# power.net
KiCad netlist of a schematic drawn in Altium Designer
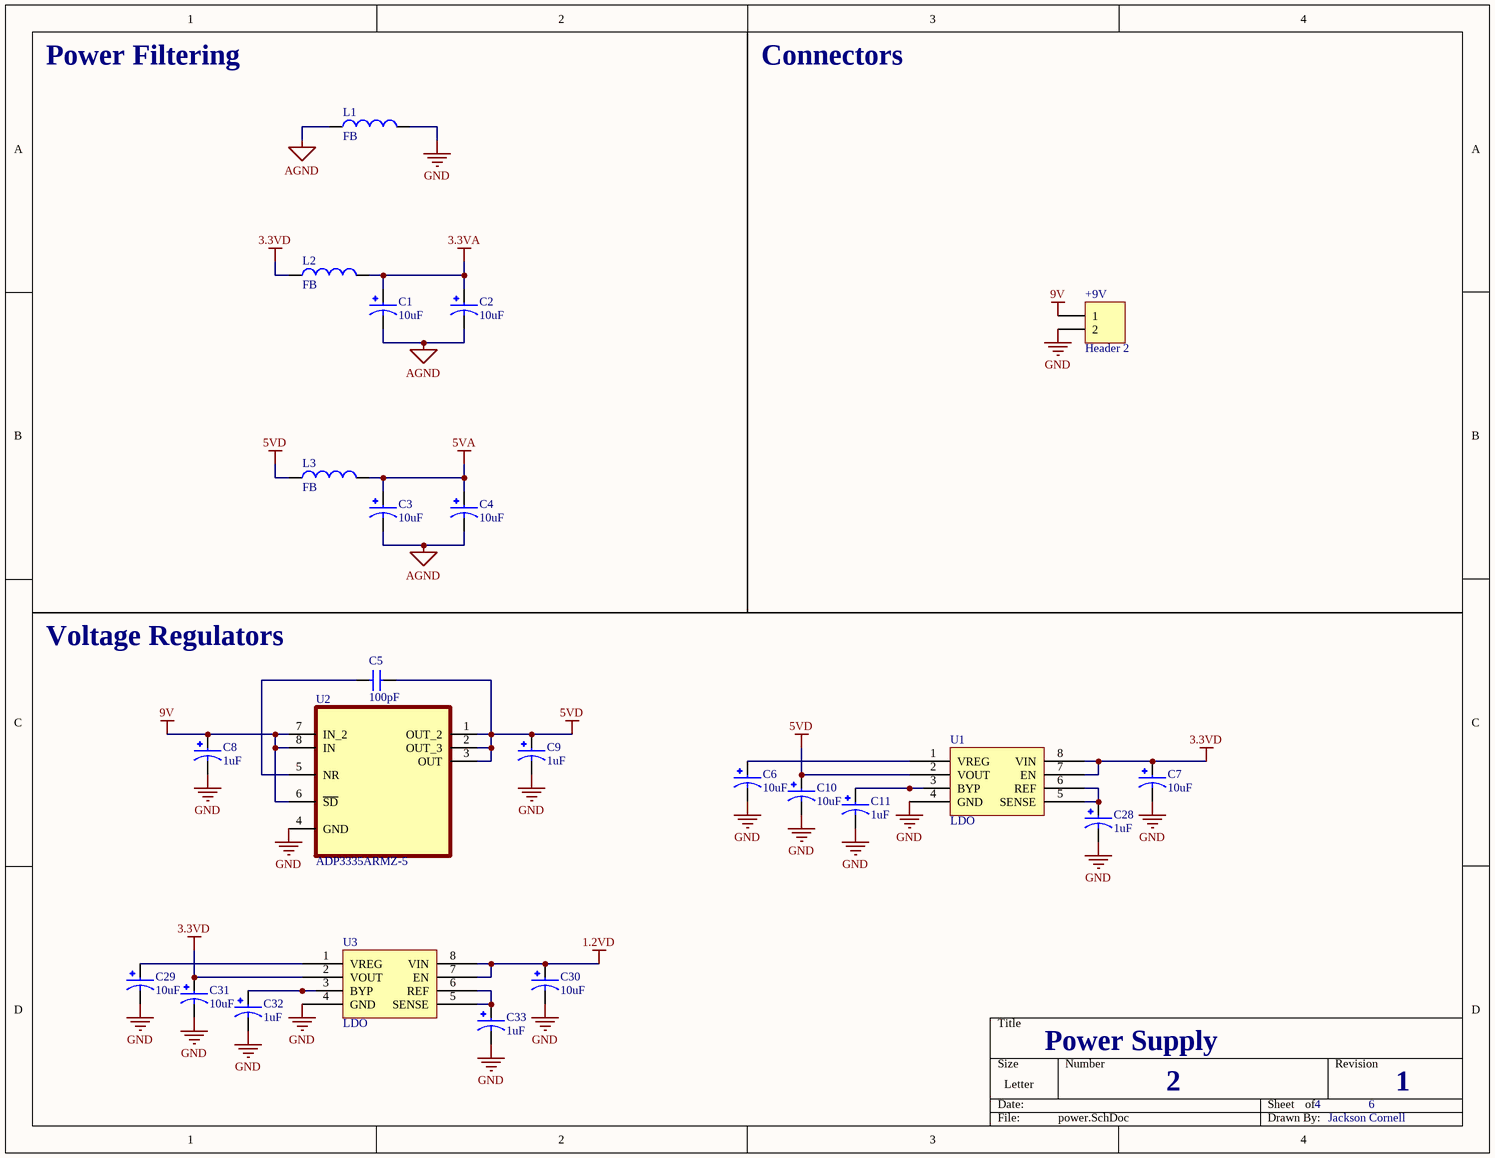
[diagram p0: power.SchDoc]

(export (version "E")
  (design (tool "Eeschema 10.0.6"))
  (components
    (comp (ref "+9V")
      (value "Header 2")
      (footprint "HDR1X2")
      (description "Header, 2-Pin")
      (fields (field (name "PUBLISHER") "Altium Limited"))
      (libsource (lib "Miscellaneous Connectors") (part "Header 2"))
    )
    (comp (ref "C1")
      (value "10uF")
      (footprint "CAPPRD500W50D500H1100")
      (description "Aluminum Electrolytic Capacitors, 220uF, 6.3V, -40 to 105C")
      (fields (field (name "MF") "Panasonic") (field (name "MP") "EEUFS0J221B"))
      (libsource (lib "EEUFS0J221B") (part "EEUFS0J221B"))
    )
    (comp (ref "C2")
      (value "10uF")
      (footprint "CAPPRD500W50D500H1100")
      (description "Aluminum Electrolytic Capacitors, 220uF, 6.3V, -40 to 105C")
      (fields (field (name "MF") "Panasonic") (field (name "MP") "EEUFS0J221B"))
      (libsource (lib "EEUFS0J221B") (part "EEUFS0J221B"))
    )
    (comp (ref "C3")
      (value "10uF")
      (footprint "CAPPRD500W50D500H1100")
      (description "Aluminum Electrolytic Capacitors, 220uF, 6.3V, -40 to 105C")
      (fields (field (name "MF") "Panasonic") (field (name "MP") "EEUFS0J221B"))
      (libsource (lib "EEUFS0J221B") (part "EEUFS0J221B"))
    )
    (comp (ref "C4")
      (value "10uF")
      (footprint "CAPPRD500W50D500H1100")
      (description "Aluminum Electrolytic Capacitors, 220uF, 6.3V, -40 to 105C")
      (fields (field (name "MF") "Panasonic") (field (name "MP") "EEUFS0J221B"))
      (libsource (lib "EEUFS0J221B") (part "EEUFS0J221B"))
    )
    (comp (ref "C5")
      (value "100pF")
      (footprint "CAPC0805")
      (fields (field (name "Comment") "Cap"))
      (libsource (lib "Passives") (part "Cap"))
    )
    (comp (ref "C6")
      (value "10uF")
      (footprint "CAPPRD500W50D500H1100")
      (description "Aluminum Electrolytic Capacitors, 220uF, 6.3V, -40 to 105C")
      (fields (field (name "MF") "Panasonic") (field (name "MP") "EEUFS0J221B"))
      (libsource (lib "EEUFS0J221B") (part "EEUFS0J221B"))
    )
    (comp (ref "C7")
      (value "10uF")
      (footprint "CAPPRD500W50D500H1100")
      (description "Aluminum Electrolytic Capacitors, 220uF, 6.3V, -40 to 105C")
      (fields (field (name "MF") "Panasonic") (field (name "MP") "EEUFS0J221B"))
      (libsource (lib "EEUFS0J221B") (part "EEUFS0J221B"))
    )
    (comp (ref "C8")
      (value "1uF")
      (footprint "CAPPRD500W50D500H1100")
      (description "Aluminum Electrolytic Capacitors, 220uF, 6.3V, -40 to 105C")
      (fields (field (name "MF") "Panasonic") (field (name "MP") "EEUFS0J221B"))
      (libsource (lib "EEUFS0J221B") (part "EEUFS0J221B"))
    )
    (comp (ref "C9")
      (value "1uF")
      (footprint "CAPPRD500W50D500H1100")
      (description "Aluminum Electrolytic Capacitors, 220uF, 6.3V, -40 to 105C")
      (fields (field (name "MF") "Panasonic") (field (name "MP") "EEUFS0J221B"))
      (libsource (lib "EEUFS0J221B") (part "EEUFS0J221B"))
    )
    (comp (ref "C10")
      (value "10uF")
      (footprint "CAPPRD500W50D500H1100")
      (description "Aluminum Electrolytic Capacitors, 220uF, 6.3V, -40 to 105C")
      (fields (field (name "MF") "Panasonic") (field (name "MP") "EEUFS0J221B"))
      (libsource (lib "EEUFS0J221B") (part "EEUFS0J221B"))
    )
    (comp (ref "C11")
      (value "1uF")
      (footprint "CAPPRD500W50D500H1100")
      (description "Aluminum Electrolytic Capacitors, 220uF, 6.3V, -40 to 105C")
      (fields (field (name "MF") "Panasonic") (field (name "MP") "EEUFS0J221B"))
      (libsource (lib "EEUFS0J221B") (part "EEUFS0J221B"))
    )
    (comp (ref "C28")
      (value "1uF")
      (footprint "CAPPRD500W50D500H1100")
      (description "Aluminum Electrolytic Capacitors, 220uF, 6.3V, -40 to 105C")
      (fields (field (name "MF") "Panasonic") (field (name "MP") "EEUFS0J221B"))
      (libsource (lib "EEUFS0J221B") (part "EEUFS0J221B"))
    )
    (comp (ref "C29")
      (value "10uF")
      (footprint "CAPPRD500W50D500H1100")
      (description "Aluminum Electrolytic Capacitors, 220uF, 6.3V, -40 to 105C")
      (fields (field (name "MF") "Panasonic") (field (name "MP") "EEUFS0J221B"))
      (libsource (lib "EEUFS0J221B") (part "EEUFS0J221B"))
    )
    (comp (ref "C30")
      (value "10uF")
      (footprint "CAPPRD500W50D500H1100")
      (description "Aluminum Electrolytic Capacitors, 220uF, 6.3V, -40 to 105C")
      (fields (field (name "MF") "Panasonic") (field (name "MP") "EEUFS0J221B"))
      (libsource (lib "EEUFS0J221B") (part "EEUFS0J221B"))
    )
    (comp (ref "C31")
      (value "10uF")
      (footprint "CAPPRD500W50D500H1100")
      (description "Aluminum Electrolytic Capacitors, 220uF, 6.3V, -40 to 105C")
      (fields (field (name "MF") "Panasonic") (field (name "MP") "EEUFS0J221B"))
      (libsource (lib "EEUFS0J221B") (part "EEUFS0J221B"))
    )
    (comp (ref "C32")
      (value "1uF")
      (footprint "CAPPRD500W50D500H1100")
      (description "Aluminum Electrolytic Capacitors, 220uF, 6.3V, -40 to 105C")
      (fields (field (name "MF") "Panasonic") (field (name "MP") "EEUFS0J221B"))
      (libsource (lib "EEUFS0J221B") (part "EEUFS0J221B"))
    )
    (comp (ref "C33")
      (value "1uF")
      (footprint "CAPPRD500W50D500H1100")
      (description "Aluminum Electrolytic Capacitors, 220uF, 6.3V, -40 to 105C")
      (fields (field (name "MF") "Panasonic") (field (name "MP") "EEUFS0J221B"))
      (libsource (lib "EEUFS0J221B") (part "EEUFS0J221B"))
    )
    (comp (ref "L1")
      (value "FB")
      (footprint "RES0805")
      (description "Inductor")
      (fields (field (name "PUBLISHER") "Altium Limited"))
      (libsource (lib "Miscellaneous Devices") (part "Inductor"))
    )
    (comp (ref "L2")
      (value "FB")
      (footprint "RES0805")
      (description "Inductor")
      (fields (field (name "PUBLISHER") "Altium Limited"))
      (libsource (lib "Miscellaneous Devices") (part "Inductor"))
    )
    (comp (ref "L3")
      (value "FB")
      (footprint "RES0805")
      (description "Inductor")
      (fields (field (name "PUBLISHER") "Altium Limited"))
      (libsource (lib "Miscellaneous Devices") (part "Inductor"))
    )
    (comp (ref "U1")
      (value "LDO")
      (footprint "SOIC127P600X175-9N")
      (libsource (lib "ADM7154") (part "ADM7154"))
    )
    (comp (ref "U2")
      (value "ADP3335ARMZ-5")
      (footprint "SOP65P490X110-8N")
      (description "Linear Voltage Regulator IC 1 Output 500mA 8-MSOP")
      (fields (field (name "MP") "ADP3335ARMZ-3.3") (field (name "MF") "Analog Devices"))
      (libsource (lib "ADP3335ARMZ-3.3") (part "ADP3335ARMZ-3.3"))
    )
    (comp (ref "U3")
      (value "LDO")
      (footprint "SOIC127P600X175-9N")
      (libsource (lib "ADM7154") (part "ADM7154"))
    )
  )
  (nets
    (net (code "1") (name "1.2VD") (class "Default")
      (node (ref "C30") (pin "P") (pinfunction "P_P") (pintype "passive"))
      (node (ref "U3") (pin "7") (pinfunction "EN_7") (pintype "passive"))
      (node (ref "U3") (pin "8") (pinfunction "VIN_8") (pintype "passive"))
    )
    (net (code "2") (name "3.3VA") (class "Default")
      (node (ref "C1") (pin "P") (pinfunction "P_P") (pintype "passive"))
      (node (ref "C2") (pin "P") (pinfunction "P_P") (pintype "passive"))
      (node (ref "L2") (pin "2") (pinfunction "2_2") (pintype "passive"))
    )
    (net (code "3") (name "3.3VD") (class "Default")
      (node (ref "C31") (pin "P") (pinfunction "P_P") (pintype "passive"))
      (node (ref "C7") (pin "P") (pinfunction "P_P") (pintype "passive"))
      (node (ref "L2") (pin "1") (pinfunction "1_1") (pintype "passive"))
      (node (ref "U1") (pin "7") (pinfunction "EN_7") (pintype "passive"))
      (node (ref "U1") (pin "8") (pinfunction "VIN_8") (pintype "passive"))
      (node (ref "U3") (pin "2") (pinfunction "VOUT_2") (pintype "passive"))
    )
    (net (code "4") (name "5VA") (class "Default")
      (node (ref "C3") (pin "P") (pinfunction "P_P") (pintype "passive"))
      (node (ref "C4") (pin "P") (pinfunction "P_P") (pintype "passive"))
      (node (ref "L3") (pin "2") (pinfunction "2_2") (pintype "passive"))
    )
    (net (code "5") (name "5VD") (class "Default")
      (node (ref "C10") (pin "P") (pinfunction "P_P") (pintype "passive"))
      (node (ref "C5") (pin "2") (pinfunction "B_2") (pintype "passive"))
      (node (ref "C9") (pin "P") (pinfunction "P_P") (pintype "passive"))
      (node (ref "L3") (pin "1") (pinfunction "1_1") (pintype "passive"))
      (node (ref "U1") (pin "2") (pinfunction "VOUT_2") (pintype "passive"))
      (node (ref "U2") (pin "1") (pinfunction "OUT_2_1") (pintype "passive"))
      (node (ref "U2") (pin "2") (pinfunction "OUT_3_2") (pintype "passive"))
      (node (ref "U2") (pin "3") (pinfunction "OUT_3") (pintype "passive"))
    )
    (net (code "6") (name "9V") (class "Default")
      (node (ref "+9V") (pin "1") (pinfunction "1_1") (pintype "passive"))
      (node (ref "C8") (pin "P") (pinfunction "P_P") (pintype "passive"))
      (node (ref "U2") (pin "6") (pinfunction "~{SD}_6") (pintype "passive"))
      (node (ref "U2") (pin "7") (pinfunction "IN_2_7") (pintype "passive"))
      (node (ref "U2") (pin "8") (pinfunction "IN_8") (pintype "passive"))
    )
    (net (code "7") (name "AGND") (class "Default")
      (node (ref "C1") (pin "N") (pinfunction "N_N") (pintype "passive"))
      (node (ref "C2") (pin "N") (pinfunction "N_N") (pintype "passive"))
      (node (ref "C3") (pin "N") (pinfunction "N_N") (pintype "passive"))
      (node (ref "C4") (pin "N") (pinfunction "N_N") (pintype "passive"))
      (node (ref "L1") (pin "1") (pinfunction "1_1") (pintype "passive"))
    )
    (net (code "8") (name "GND") (class "Default")
      (node (ref "+9V") (pin "2") (pinfunction "2_2") (pintype "passive"))
      (node (ref "C10") (pin "N") (pinfunction "N_N") (pintype "passive"))
      (node (ref "C11") (pin "N") (pinfunction "N_N") (pintype "passive"))
      (node (ref "C28") (pin "N") (pinfunction "N_N") (pintype "passive"))
      (node (ref "C29") (pin "N") (pinfunction "N_N") (pintype "passive"))
      (node (ref "C30") (pin "N") (pinfunction "N_N") (pintype "passive"))
      (node (ref "C31") (pin "N") (pinfunction "N_N") (pintype "passive"))
      (node (ref "C32") (pin "N") (pinfunction "N_N") (pintype "passive"))
      (node (ref "C33") (pin "N") (pinfunction "N_N") (pintype "passive"))
      (node (ref "C6") (pin "N") (pinfunction "N_N") (pintype "passive"))
      (node (ref "C7") (pin "N") (pinfunction "N_N") (pintype "passive"))
      (node (ref "C8") (pin "N") (pinfunction "N_N") (pintype "passive"))
      (node (ref "C9") (pin "N") (pinfunction "N_N") (pintype "passive"))
      (node (ref "L1") (pin "2") (pinfunction "2_2") (pintype "passive"))
      (node (ref "U1") (pin "4") (pinfunction "GND_4") (pintype "passive"))
      (node (ref "U2") (pin "4") (pinfunction "GND_4") (pintype "passive"))
      (node (ref "U3") (pin "4") (pinfunction "GND_4") (pintype "passive"))
    )
    (net (code "9") (name "Net-(C5-A)") (class "Default")
      (node (ref "C5") (pin "1") (pinfunction "A_1") (pintype "passive"))
      (node (ref "U2") (pin "5") (pinfunction "NR_5") (pintype "passive"))
    )
    (net (code "10") (name "Net-(U1-BYP)") (class "Default")
      (node (ref "C11") (pin "P") (pinfunction "P_P") (pintype "passive"))
      (node (ref "U1") (pin "3") (pinfunction "BYP_3") (pintype "passive"))
    )
    (net (code "11") (name "Net-(U1-REF)") (class "Default")
      (node (ref "C28") (pin "P") (pinfunction "P_P") (pintype "passive"))
      (node (ref "U1") (pin "5") (pinfunction "SENSE_5") (pintype "passive"))
      (node (ref "U1") (pin "6") (pinfunction "REF_6") (pintype "passive"))
    )
    (net (code "12") (name "Net-(U1-VREG)") (class "Default")
      (node (ref "C6") (pin "P") (pinfunction "P_P") (pintype "passive"))
      (node (ref "U1") (pin "1") (pinfunction "VREG_1") (pintype "passive"))
    )
    (net (code "13") (name "Net-(U3-BYP)") (class "Default")
      (node (ref "C32") (pin "P") (pinfunction "P_P") (pintype "passive"))
      (node (ref "U3") (pin "3") (pinfunction "BYP_3") (pintype "passive"))
    )
    (net (code "14") (name "Net-(U3-REF)") (class "Default")
      (node (ref "C33") (pin "P") (pinfunction "P_P") (pintype "passive"))
      (node (ref "U3") (pin "5") (pinfunction "SENSE_5") (pintype "passive"))
      (node (ref "U3") (pin "6") (pinfunction "REF_6") (pintype "passive"))
    )
    (net (code "15") (name "Net-(U3-VREG)") (class "Default")
      (node (ref "C29") (pin "P") (pinfunction "P_P") (pintype "passive"))
      (node (ref "U3") (pin "1") (pinfunction "VREG_1") (pintype "passive"))
    )
  )
)
